# TalonPortBreakout.net
KiCad netlist of a schematic drawn in EAGLE
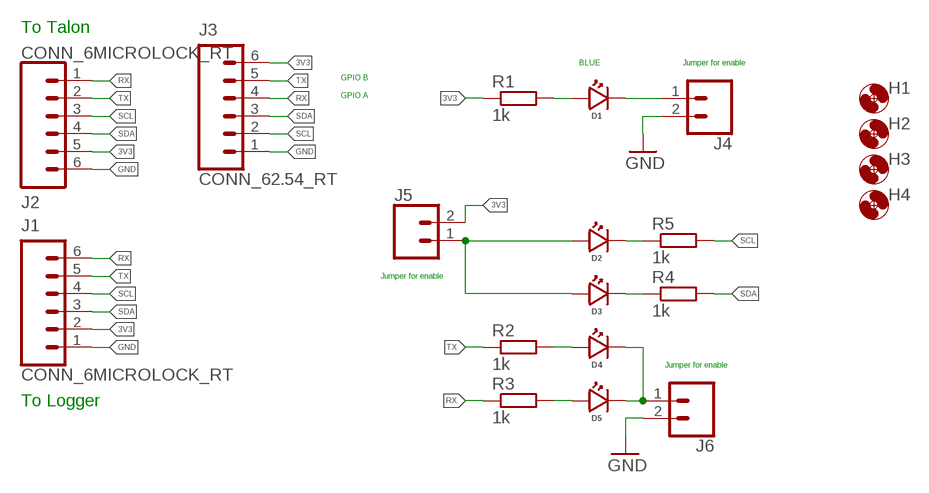
[diagram p0: schematic, sheet 1]

(export (version "E")
  (design (tool "Eeschema 10.0.6"))
  (components
    (comp (ref "D1")
      (value "LEDBLUE0603")
      (footprint "eagle-import:LED_0603")
      (fields (field (name "MF") "Wurth") (field (name "MPN") "150060BS75000"))
      (libsource (lib "eagle-import") (part "LED0603BLUE"))
    )
    (comp (ref "D2")
      (value "LEDAMBER0603")
      (footprint "eagle-import:LED_0603")
      (fields (field (name "MF") "Wurth") (field (name "MPN") "150060AS75000"))
      (libsource (lib "eagle-import") (part "LED0603AMBER"))
    )
    (comp (ref "D3")
      (value "LEDAMBER0603")
      (footprint "eagle-import:LED_0603")
      (fields (field (name "MF") "Wurth") (field (name "MPN") "150060AS75000"))
      (libsource (lib "eagle-import") (part "LED0603AMBER"))
    )
    (comp (ref "D4")
      (value "LEDGREEN0603")
      (footprint "eagle-import:LED_0603")
      (fields (field (name "MF") "Wurth") (field (name "MPN") "150060GS75000"))
      (libsource (lib "eagle-import") (part "LED0603GREEN"))
    )
    (comp (ref "D5")
      (value "LEDRED0603")
      (footprint "eagle-import:LED_0603")
      (fields (field (name "MF") "Wurth") (field (name "MPN") "150060RS75000"))
      (libsource (lib "eagle-import") (part "LED0603RED"))
    )
    (comp (ref "H1")
      (value "MOUNTING_HOLE2_NP")
      (footprint "eagle-import:2_56")
      (fields (field (name "MPN") "DNP"))
      (libsource (lib "eagle-import") (part "MOUNTING_HOLE2_NP"))
    )
    (comp (ref "H2")
      (value "MOUNTING_HOLE2_NP")
      (footprint "eagle-import:2_56")
      (fields (field (name "MPN") "DNP"))
      (libsource (lib "eagle-import") (part "MOUNTING_HOLE2_NP"))
    )
    (comp (ref "H3")
      (value "MOUNTING_HOLE2_NP")
      (footprint "eagle-import:2_56")
      (fields (field (name "MPN") "DNP"))
      (libsource (lib "eagle-import") (part "MOUNTING_HOLE2_NP"))
    )
    (comp (ref "H4")
      (value "MOUNTING_HOLE2_NP")
      (footprint "eagle-import:2_56")
      (fields (field (name "MPN") "DNP"))
      (libsource (lib "eagle-import") (part "MOUNTING_HOLE2_NP"))
    )
    (comp (ref "J1")
      (value "CONN_6MICROLOCK_RT")
      (footprint "eagle-import:1X06_MICROLOCKPLUS_RT")
      (fields (field (name "MF") "Molex") (field (name "MPN") "5055670681"))
      (libsource (lib "eagle-import") (part "CONN_6MICROLOCK_RT"))
    )
    (comp (ref "J2")
      (value "CONN_6MICROLOCK_RT")
      (footprint "eagle-import:1X06_MICROLOCKPLUS_RT")
      (fields (field (name "MF") "Molex") (field (name "MPN") "5055670681"))
      (libsource (lib "eagle-import") (part "CONN_6MICROLOCK_RT"))
    )
    (comp (ref "J3")
      (value "CONN_62.54_RT")
      (footprint "eagle-import:1X06_90")
      (libsource (lib "eagle-import") (part "CONN_62.54_RT"))
    )
    (comp (ref "J4")
      (value "CONN_02")
      (footprint "eagle-import:1X02")
      (libsource (lib "eagle-import") (part "CONN_02"))
    )
    (comp (ref "J5")
      (value "CONN_02")
      (footprint "eagle-import:1X02")
      (libsource (lib "eagle-import") (part "CONN_02"))
    )
    (comp (ref "J6")
      (value "CONN_02")
      (footprint "eagle-import:1X02")
      (libsource (lib "eagle-import") (part "CONN_02"))
    )
    (comp (ref "R1")
      (value "1k")
      (footprint "eagle-import:R0402")
      (fields (field (name "MF") "Yageo") (field (name "MPN") "RC0402FR-071KL"))
      (libsource (lib "eagle-import") (part "R-EU_R04021K"))
    )
    (comp (ref "R2")
      (value "1k")
      (footprint "eagle-import:R0402")
      (fields (field (name "MF") "Yageo") (field (name "MPN") "RC0402FR-071KL"))
      (libsource (lib "eagle-import") (part "R-EU_R04021K"))
    )
    (comp (ref "R3")
      (value "1k")
      (footprint "eagle-import:R0402")
      (fields (field (name "MF") "Yageo") (field (name "MPN") "RC0402FR-071KL"))
      (libsource (lib "eagle-import") (part "R-EU_R04021K"))
    )
    (comp (ref "R4")
      (value "1k")
      (footprint "eagle-import:R0402")
      (fields (field (name "MF") "Yageo") (field (name "MPN") "RC0402FR-071KL"))
      (libsource (lib "eagle-import") (part "R-EU_R04021K"))
    )
    (comp (ref "R5")
      (value "1k")
      (footprint "eagle-import:R0402")
      (fields (field (name "MF") "Yageo") (field (name "MPN") "RC0402FR-071KL"))
      (libsource (lib "eagle-import") (part "R-EU_R04021K"))
    )
  )
  (nets
    (net (code "1") (name "3V3") (class "Default")
      (node (ref "J1") (pin "2") (pinfunction "2_2") (pintype "passive"))
      (node (ref "J2") (pin "5") (pinfunction "5_5") (pintype "passive"))
      (node (ref "J3") (pin "6") (pinfunction "6_6") (pintype "passive"))
      (node (ref "J5") (pin "2") (pinfunction "2_2") (pintype "passive"))
      (node (ref "R1") (pin "1") (pinfunction "1_1") (pintype "passive"))
    )
    (net (code "2") (name "GND") (class "Default")
      (node (ref "J1") (pin "1") (pinfunction "1_1") (pintype "passive"))
      (node (ref "J2") (pin "6") (pinfunction "6_6") (pintype "passive"))
      (node (ref "J3") (pin "1") (pinfunction "1_1") (pintype "passive"))
      (node (ref "J4") (pin "2") (pinfunction "2_2") (pintype "passive"))
      (node (ref "J6") (pin "2") (pinfunction "2_2") (pintype "passive"))
    )
    (net (code "3") (name "Net-(D1-PadANODE)") (class "Default")
      (node (ref "D1") (pin "ANODE") (pinfunction "ANODE_ANODE") (pintype "power_in"))
      (node (ref "R1") (pin "2") (pinfunction "2_2") (pintype "passive"))
    )
    (net (code "4") (name "Net-(D1-PadCATHODE)") (class "Default")
      (node (ref "D1") (pin "CATHODE") (pinfunction "CATHODE_CATHODE") (pintype "power_in"))
      (node (ref "J4") (pin "1") (pinfunction "1_1") (pintype "passive"))
    )
    (net (code "5") (name "Net-(D2-PadANODE)") (class "Default")
      (node (ref "D2") (pin "ANODE") (pinfunction "ANODE_ANODE") (pintype "power_in"))
      (node (ref "D3") (pin "ANODE") (pinfunction "ANODE_ANODE") (pintype "power_in"))
      (node (ref "J5") (pin "1") (pinfunction "1_1") (pintype "passive"))
    )
    (net (code "6") (name "Net-(D2-PadCATHODE)") (class "Default")
      (node (ref "D2") (pin "CATHODE") (pinfunction "CATHODE_CATHODE") (pintype "power_in"))
      (node (ref "R5") (pin "1") (pinfunction "1_1") (pintype "passive"))
    )
    (net (code "7") (name "Net-(D3-PadCATHODE)") (class "Default")
      (node (ref "D3") (pin "CATHODE") (pinfunction "CATHODE_CATHODE") (pintype "power_in"))
      (node (ref "R4") (pin "1") (pinfunction "1_1") (pintype "passive"))
    )
    (net (code "8") (name "Net-(D4-PadANODE)") (class "Default")
      (node (ref "D4") (pin "ANODE") (pinfunction "ANODE_ANODE") (pintype "power_in"))
      (node (ref "R2") (pin "2") (pinfunction "2_2") (pintype "passive"))
    )
    (net (code "9") (name "Net-(D4-PadCATHODE)") (class "Default")
      (node (ref "D4") (pin "CATHODE") (pinfunction "CATHODE_CATHODE") (pintype "power_in"))
      (node (ref "D5") (pin "CATHODE") (pinfunction "CATHODE_CATHODE") (pintype "power_in"))
      (node (ref "J6") (pin "1") (pinfunction "1_1") (pintype "passive"))
    )
    (net (code "10") (name "Net-(D5-PadANODE)") (class "Default")
      (node (ref "D5") (pin "ANODE") (pinfunction "ANODE_ANODE") (pintype "power_in"))
      (node (ref "R3") (pin "2") (pinfunction "2_2") (pintype "passive"))
    )
    (net (code "11") (name "RX") (class "Default")
      (node (ref "J1") (pin "6") (pinfunction "6_6") (pintype "passive"))
      (node (ref "J2") (pin "1") (pinfunction "1_1") (pintype "passive"))
      (node (ref "J3") (pin "4") (pinfunction "4_4") (pintype "passive"))
      (node (ref "R3") (pin "1") (pinfunction "1_1") (pintype "passive"))
    )
    (net (code "12") (name "SCL") (class "Default")
      (node (ref "J1") (pin "4") (pinfunction "4_4") (pintype "passive"))
      (node (ref "J2") (pin "3") (pinfunction "3_3") (pintype "passive"))
      (node (ref "J3") (pin "2") (pinfunction "2_2") (pintype "passive"))
      (node (ref "R5") (pin "2") (pinfunction "2_2") (pintype "passive"))
    )
    (net (code "13") (name "SDA") (class "Default")
      (node (ref "J1") (pin "3") (pinfunction "3_3") (pintype "passive"))
      (node (ref "J2") (pin "4") (pinfunction "4_4") (pintype "passive"))
      (node (ref "J3") (pin "3") (pinfunction "3_3") (pintype "passive"))
      (node (ref "R4") (pin "2") (pinfunction "2_2") (pintype "passive"))
    )
    (net (code "14") (name "TX") (class "Default")
      (node (ref "J1") (pin "5") (pinfunction "5_5") (pintype "passive"))
      (node (ref "J2") (pin "2") (pinfunction "2_2") (pintype "passive"))
      (node (ref "J3") (pin "5") (pinfunction "5_5") (pintype "passive"))
      (node (ref "R2") (pin "1") (pinfunction "1_1") (pintype "passive"))
    )
  )
)
